# brain.net
KiCad netlist of a schematic drawn in EAGLE
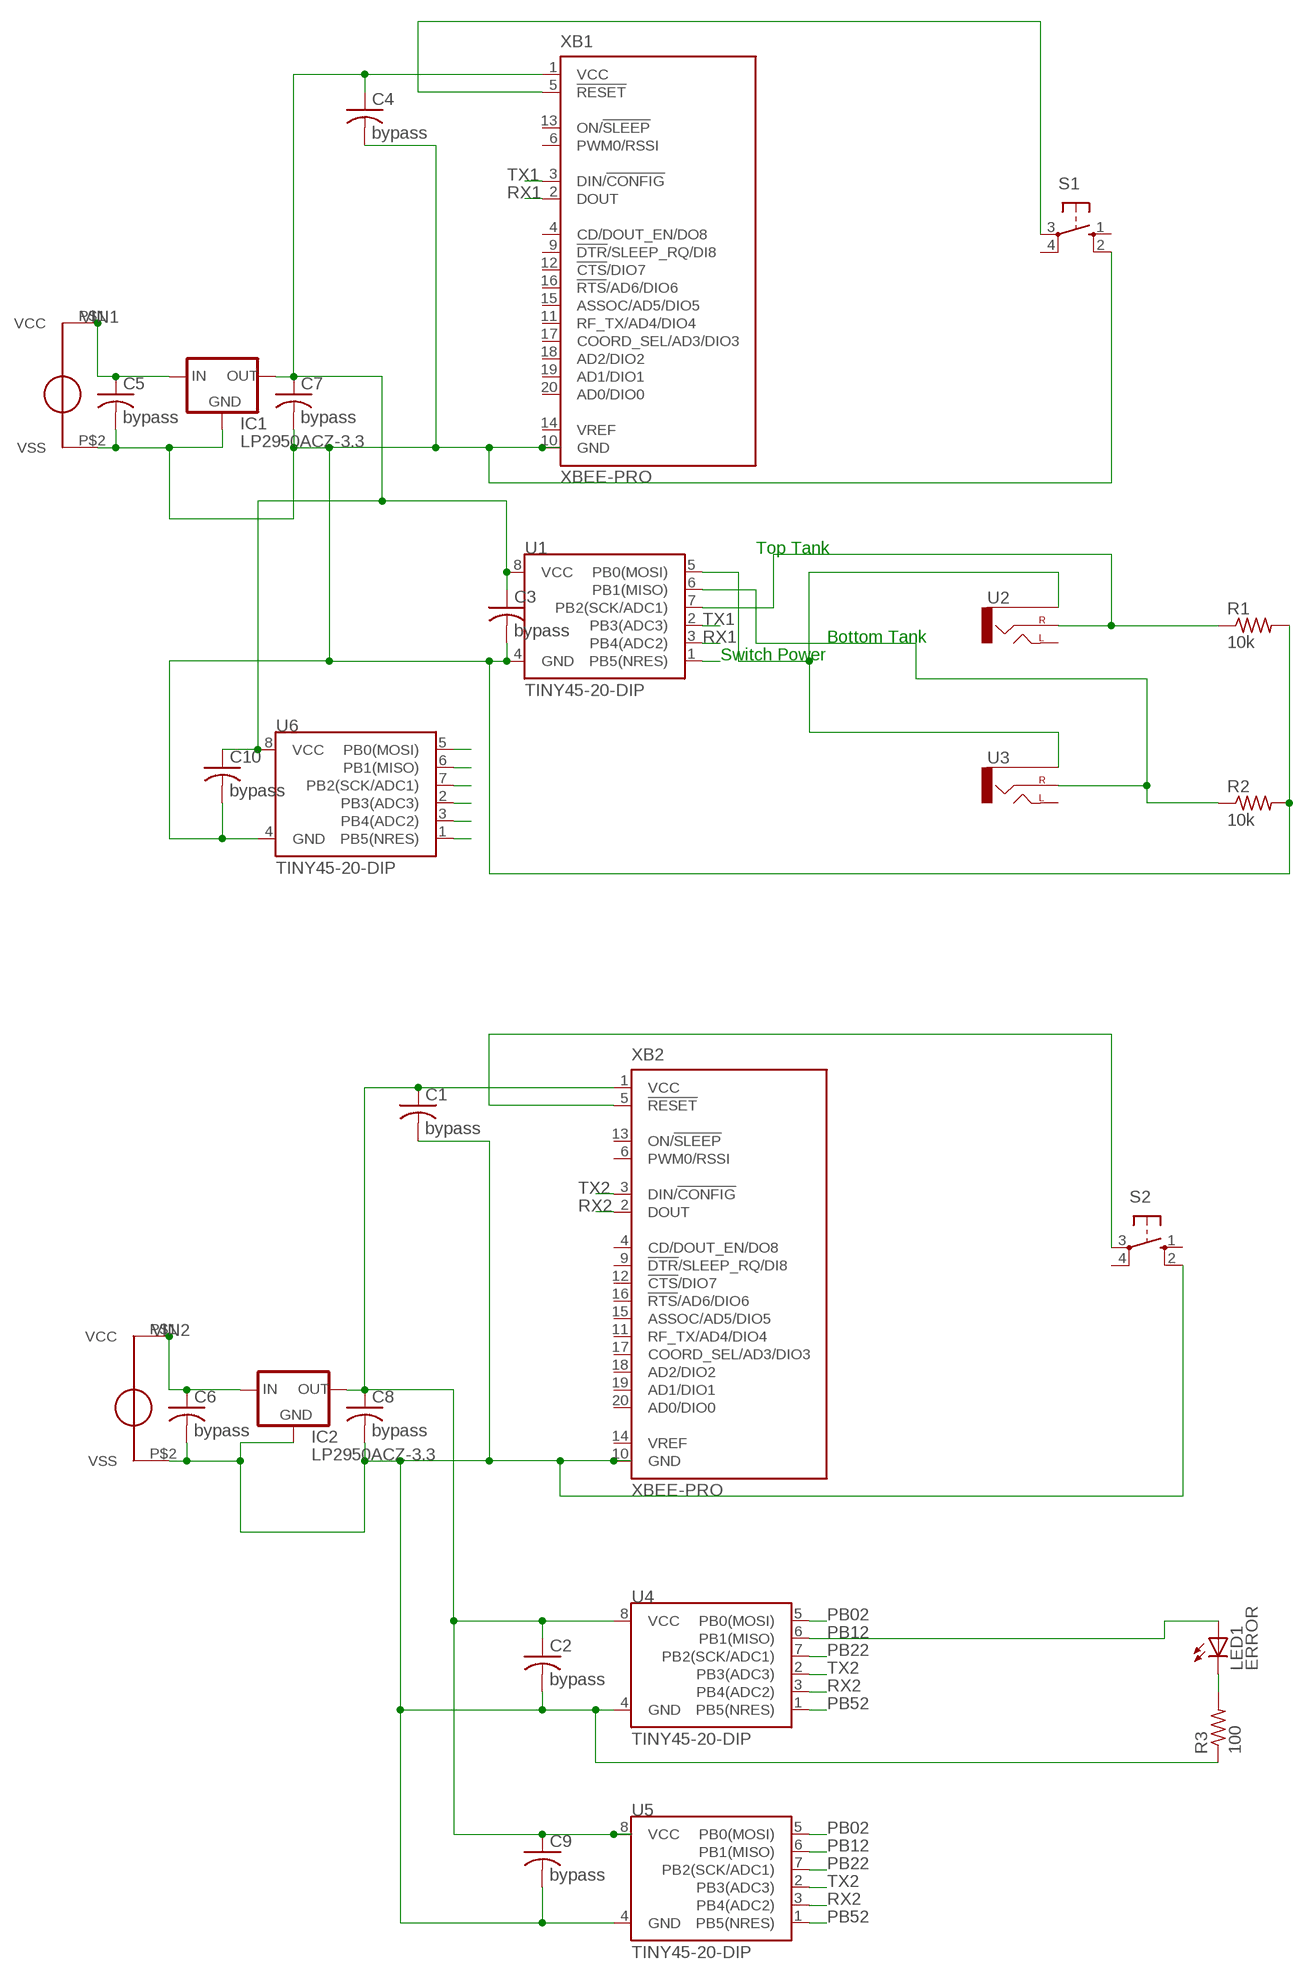
[diagram p0: schematic, sheet 1]

(export (version "E")
  (design (tool "Eeschema 10.0.6"))
  (components
    (comp (ref "C1")
      (value "bypass")
      (footprint "eagle-import:C050-025X075")
      (libsource (lib "eagle-import") (part "C-US050-025X075"))
    )
    (comp (ref "C2")
      (value "bypass")
      (footprint "eagle-import:C050-025X075")
      (libsource (lib "eagle-import") (part "C-US050-025X075"))
    )
    (comp (ref "C3")
      (value "bypass")
      (footprint "eagle-import:C050-025X075")
      (libsource (lib "eagle-import") (part "C-US050-025X075"))
    )
    (comp (ref "C4")
      (value "bypass")
      (footprint "eagle-import:C050-025X075")
      (libsource (lib "eagle-import") (part "C-US050-025X075"))
    )
    (comp (ref "C5")
      (value "bypass")
      (footprint "eagle-import:C050-025X075")
      (libsource (lib "eagle-import") (part "C-US050-025X075"))
    )
    (comp (ref "C6")
      (value "bypass")
      (footprint "eagle-import:C050-025X075")
      (libsource (lib "eagle-import") (part "C-US050-025X075"))
    )
    (comp (ref "C7")
      (value "bypass")
      (footprint "eagle-import:C050-025X075")
      (libsource (lib "eagle-import") (part "C-US050-025X075"))
    )
    (comp (ref "C8")
      (value "bypass")
      (footprint "eagle-import:C050-025X075")
      (libsource (lib "eagle-import") (part "C-US050-025X075"))
    )
    (comp (ref "C9")
      (value "bypass")
      (footprint "eagle-import:C050-025X075")
      (libsource (lib "eagle-import") (part "C-US050-025X075"))
    )
    (comp (ref "C10")
      (value "bypass")
      (footprint "eagle-import:C050-025X075")
      (libsource (lib "eagle-import") (part "C-US050-025X075"))
    )
    (comp (ref "IC1")
      (value "LP2950ACZ-3.3")
      (footprint "eagle-import:TO92")
      (libsource (lib "eagle-import") (part "LP2950?ACZ-3.3"))
    )
    (comp (ref "IC2")
      (value "LP2950ACZ-3.3")
      (footprint "eagle-import:TO92")
      (libsource (lib "eagle-import") (part "LP2950?ACZ-3.3"))
    )
    (comp (ref "LED1")
      (value "ERROR")
      (footprint "eagle-import:LED3MM")
      (libsource (lib "eagle-import") (part "LED3MM"))
    )
    (comp (ref "R1")
      (value "10k")
      (footprint "eagle-import:0207_10")
      (fields (field (name "MPN") "LT3652EMSE#PBF"))
      (libsource (lib "eagle-import") (part "R-US_0207/10"))
    )
    (comp (ref "R2")
      (value "10k")
      (footprint "eagle-import:0207_10")
      (fields (field (name "MPN") "LT3652EMSE#PBF"))
      (libsource (lib "eagle-import") (part "R-US_0207/10"))
    )
    (comp (ref "R3")
      (value "100")
      (footprint "eagle-import:0207_10")
      (fields (field (name "MPN") "LT3652EMSE#PBF"))
      (libsource (lib "eagle-import") (part "R-US_0207/10"))
    )
    (comp (ref "S1")
      (value "10-XX")
      (footprint "eagle-import:B3F-10XX")
      (fields (field (name "MPN") "B3F-1000"))
      (libsource (lib "eagle-import") (part "10-XX"))
    )
    (comp (ref "S2")
      (value "10-XX")
      (footprint "eagle-import:B3F-10XX")
      (fields (field (name "MPN") "B3F-1000"))
      (libsource (lib "eagle-import") (part "10-XX"))
    )
    (comp (ref "U$3")
      (value "SUNNYBUDDYMOUNT")
      (footprint "eagle-import:SUNNYBUDDYMOUNT")
      (libsource (lib "eagle-import") (part "SUNNYBUDDYMOUNT"))
    )
    (comp (ref "U$6")
      (value "SUNNYBUDDYMOUNT")
      (footprint "eagle-import:SUNNYBUDDYMOUNT")
      (libsource (lib "eagle-import") (part "SUNNYBUDDYMOUNT"))
    )
    (comp (ref "U1")
      (value "TINY45-20-DIP")
      (footprint "eagle-import:DIP08")
      (libsource (lib "eagle-import") (part "ATTINY45TINY45-20-DIP"))
    )
    (comp (ref "U2")
      (value "AUDIO-JACKPTH")
      (footprint "eagle-import:AUDIO-JACK")
      (libsource (lib "eagle-import") (part "AUDIO-JACKPTH"))
    )
    (comp (ref "U3")
      (value "AUDIO-JACKPTH")
      (footprint "eagle-import:AUDIO-JACK")
      (libsource (lib "eagle-import") (part "AUDIO-JACKPTH"))
    )
    (comp (ref "U4")
      (value "TINY45-20-DIP")
      (footprint "eagle-import:DIP08")
      (libsource (lib "eagle-import") (part "ATTINY45TINY45-20-DIP"))
    )
    (comp (ref "U5")
      (value "TINY45-20-DIP")
      (footprint "eagle-import:DIP08")
      (libsource (lib "eagle-import") (part "ATTINY45TINY45-20-DIP"))
    )
    (comp (ref "U6")
      (value "TINY45-20-DIP")
      (footprint "eagle-import:DIP08")
      (libsource (lib "eagle-import") (part "ATTINY45TINY45-20-DIP"))
    )
    (comp (ref "XB1")
      (value "XBEE-PRO")
      (footprint "eagle-import:XBEE-PRO")
      (fields (field (name "MPN") "XBP24-AWI-001") (field (name "OC_NEWARK") "unknown"))
      (libsource (lib "eagle-import") (part "XBEE-PRO"))
    )
    (comp (ref "XB2")
      (value "XBEE-PRO")
      (footprint "eagle-import:XBEE-PRO")
      (fields (field (name "MPN") "XBP24-AWI-001") (field (name "OC_NEWARK") "unknown"))
      (libsource (lib "eagle-import") (part "XBEE-PRO"))
    )
  )
  (nets
    (net (code "1") (name "/PB01") (class "Default")
      (node (ref "U1") (pin "5") (pinfunction "PB0(MOSI)_5") (pintype "bidirectional"))
      (node (ref "U2") (pin "SLEEVE") (pinfunction "SLEEVE_SLEEVE") (pintype "bidirectional"))
      (node (ref "U3") (pin "SLEEVE") (pinfunction "SLEEVE_SLEEVE") (pintype "bidirectional"))
      (node (ref "U6") (pin "5") (pinfunction "PB0(MOSI)_5") (pintype "bidirectional"))
    )
    (net (code "2") (name "/PB02") (class "Default")
      (node (ref "U4") (pin "5") (pinfunction "PB0(MOSI)_5") (pintype "bidirectional"))
      (node (ref "U5") (pin "5") (pinfunction "PB0(MOSI)_5") (pintype "bidirectional"))
    )
    (net (code "3") (name "/PB11") (class "Default")
      (node (ref "R2") (pin "1") (pinfunction "1_1") (pintype "passive"))
      (node (ref "U1") (pin "6") (pinfunction "PB1(MISO)_6") (pintype "bidirectional"))
      (node (ref "U3") (pin "RING") (pinfunction "RIGHT_RING") (pintype "bidirectional"))
      (node (ref "U6") (pin "6") (pinfunction "PB1(MISO)_6") (pintype "bidirectional"))
    )
    (net (code "4") (name "/PB12") (class "Default")
      (node (ref "LED1") (pin "A") (pinfunction "A_A") (pintype "passive"))
      (node (ref "U4") (pin "6") (pinfunction "PB1(MISO)_6") (pintype "bidirectional"))
      (node (ref "U5") (pin "6") (pinfunction "PB1(MISO)_6") (pintype "bidirectional"))
    )
    (net (code "5") (name "/PB21") (class "Default")
      (node (ref "R1") (pin "1") (pinfunction "1_1") (pintype "passive"))
      (node (ref "U1") (pin "7") (pinfunction "PB2(SCK/ADC1)_7") (pintype "bidirectional"))
      (node (ref "U2") (pin "RING") (pinfunction "RIGHT_RING") (pintype "bidirectional"))
      (node (ref "U6") (pin "7") (pinfunction "PB2(SCK/ADC1)_7") (pintype "bidirectional"))
    )
    (net (code "6") (name "/PB22") (class "Default")
      (node (ref "U4") (pin "7") (pinfunction "PB2(SCK/ADC1)_7") (pintype "bidirectional"))
      (node (ref "U5") (pin "7") (pinfunction "PB2(SCK/ADC1)_7") (pintype "bidirectional"))
    )
    (net (code "7") (name "/PB51") (class "Default")
      (node (ref "U1") (pin "1") (pinfunction "PB5(NRES)_1") (pintype "bidirectional"))
      (node (ref "U6") (pin "1") (pinfunction "PB5(NRES)_1") (pintype "bidirectional"))
    )
    (net (code "8") (name "/PB52") (class "Default")
      (node (ref "U4") (pin "1") (pinfunction "PB5(NRES)_1") (pintype "bidirectional"))
      (node (ref "U5") (pin "1") (pinfunction "PB5(NRES)_1") (pintype "bidirectional"))
    )
    (net (code "9") (name "/RX1") (class "Default")
      (node (ref "U1") (pin "3") (pinfunction "PB4(ADC2)_3") (pintype "bidirectional"))
      (node (ref "U6") (pin "3") (pinfunction "PB4(ADC2)_3") (pintype "bidirectional"))
      (node (ref "XB1") (pin "2") (pinfunction "DOUT_2") (pintype "output"))
    )
    (net (code "10") (name "/RX2") (class "Default")
      (node (ref "U4") (pin "3") (pinfunction "PB4(ADC2)_3") (pintype "bidirectional"))
      (node (ref "U5") (pin "3") (pinfunction "PB4(ADC2)_3") (pintype "bidirectional"))
      (node (ref "XB2") (pin "2") (pinfunction "DOUT_2") (pintype "output"))
    )
    (net (code "11") (name "/TX1") (class "Default")
      (node (ref "U1") (pin "2") (pinfunction "PB3(ADC3)_2") (pintype "bidirectional"))
      (node (ref "U6") (pin "2") (pinfunction "PB3(ADC3)_2") (pintype "bidirectional"))
      (node (ref "XB1") (pin "3") (pinfunction "DIN/~{CONFIG}_3") (pintype "input"))
    )
    (net (code "12") (name "/TX2") (class "Default")
      (node (ref "U4") (pin "2") (pinfunction "PB3(ADC3)_2") (pintype "bidirectional"))
      (node (ref "U5") (pin "2") (pinfunction "PB3(ADC3)_2") (pintype "bidirectional"))
      (node (ref "XB2") (pin "3") (pinfunction "DIN/~{CONFIG}_3") (pintype "input"))
    )
    (net (code "13") (name "/VIN1") (class "Default")
      (node (ref "C5") (pin "1") (pinfunction "1_1") (pintype "passive"))
      (node (ref "IC1") (pin "3") (pinfunction "IN_3") (pintype "input"))
      (node (ref "U$3") (pin "P$1") (pinfunction "VCC_P$1") (pintype "bidirectional"))
    )
    (net (code "14") (name "/VIN2") (class "Default")
      (node (ref "C6") (pin "1") (pinfunction "1_1") (pintype "passive"))
      (node (ref "IC2") (pin "3") (pinfunction "IN_3") (pintype "input"))
      (node (ref "U$6") (pin "P$1") (pinfunction "VCC_P$1") (pintype "bidirectional"))
    )
    (net (code "15") (name "Net-(IC1-GND)") (class "Default")
      (node (ref "C10") (pin "2") (pinfunction "2_2") (pintype "passive"))
      (node (ref "C3") (pin "2") (pinfunction "2_2") (pintype "passive"))
      (node (ref "C4") (pin "2") (pinfunction "2_2") (pintype "passive"))
      (node (ref "C5") (pin "2") (pinfunction "2_2") (pintype "passive"))
      (node (ref "C7") (pin "2") (pinfunction "2_2") (pintype "passive"))
      (node (ref "IC1") (pin "2") (pinfunction "GND_2") (pintype "input"))
      (node (ref "R1") (pin "2") (pinfunction "2_2") (pintype "passive"))
      (node (ref "R2") (pin "2") (pinfunction "2_2") (pintype "passive"))
      (node (ref "S1") (pin "2") (pinfunction "S1_2") (pintype "passive"))
      (node (ref "U$3") (pin "P$2") (pinfunction "VSS_P$2") (pintype "bidirectional"))
      (node (ref "U1") (pin "4") (pinfunction "GND_4") (pintype "bidirectional"))
      (node (ref "U6") (pin "4") (pinfunction "GND_4") (pintype "bidirectional"))
      (node (ref "XB1") (pin "10") (pinfunction "GND_10") (pintype "power_in"))
    )
    (net (code "16") (name "Net-(IC1-OUT)") (class "Default")
      (node (ref "C10") (pin "1") (pinfunction "1_1") (pintype "passive"))
      (node (ref "C3") (pin "1") (pinfunction "1_1") (pintype "passive"))
      (node (ref "C4") (pin "1") (pinfunction "1_1") (pintype "passive"))
      (node (ref "C7") (pin "1") (pinfunction "1_1") (pintype "passive"))
      (node (ref "IC1") (pin "1") (pinfunction "OUT_1") (pintype "passive"))
      (node (ref "U1") (pin "8") (pinfunction "VCC_8") (pintype "bidirectional"))
      (node (ref "U6") (pin "8") (pinfunction "VCC_8") (pintype "bidirectional"))
      (node (ref "XB1") (pin "1") (pinfunction "VCC_1") (pintype "power_in"))
    )
    (net (code "17") (name "Net-(IC2-GND)") (class "Default")
      (node (ref "C1") (pin "2") (pinfunction "2_2") (pintype "passive"))
      (node (ref "C2") (pin "2") (pinfunction "2_2") (pintype "passive"))
      (node (ref "C6") (pin "2") (pinfunction "2_2") (pintype "passive"))
      (node (ref "C8") (pin "2") (pinfunction "2_2") (pintype "passive"))
      (node (ref "C9") (pin "2") (pinfunction "2_2") (pintype "passive"))
      (node (ref "IC2") (pin "2") (pinfunction "GND_2") (pintype "input"))
      (node (ref "R3") (pin "1") (pinfunction "1_1") (pintype "passive"))
      (node (ref "S2") (pin "2") (pinfunction "S1_2") (pintype "passive"))
      (node (ref "U$6") (pin "P$2") (pinfunction "VSS_P$2") (pintype "bidirectional"))
      (node (ref "U4") (pin "4") (pinfunction "GND_4") (pintype "bidirectional"))
      (node (ref "U5") (pin "4") (pinfunction "GND_4") (pintype "bidirectional"))
      (node (ref "XB2") (pin "10") (pinfunction "GND_10") (pintype "power_in"))
    )
    (net (code "18") (name "Net-(IC2-OUT)") (class "Default")
      (node (ref "C1") (pin "1") (pinfunction "1_1") (pintype "passive"))
      (node (ref "C2") (pin "1") (pinfunction "1_1") (pintype "passive"))
      (node (ref "C8") (pin "1") (pinfunction "1_1") (pintype "passive"))
      (node (ref "C9") (pin "1") (pinfunction "1_1") (pintype "passive"))
      (node (ref "IC2") (pin "1") (pinfunction "OUT_1") (pintype "passive"))
      (node (ref "U4") (pin "8") (pinfunction "VCC_8") (pintype "bidirectional"))
      (node (ref "U5") (pin "8") (pinfunction "VCC_8") (pintype "bidirectional"))
      (node (ref "XB2") (pin "1") (pinfunction "VCC_1") (pintype "power_in"))
    )
    (net (code "19") (name "Net-(LED1-C)") (class "Default")
      (node (ref "LED1") (pin "K") (pinfunction "C_K") (pintype "passive"))
      (node (ref "R3") (pin "2") (pinfunction "2_2") (pintype "passive"))
    )
    (net (code "20") (name "Net-(S1-P)") (class "Default")
      (node (ref "S1") (pin "3") (pinfunction "P_3") (pintype "passive"))
      (node (ref "XB1") (pin "5") (pinfunction "~{RESET}_5") (pintype "input"))
    )
    (net (code "21") (name "Net-(S2-P)") (class "Default")
      (node (ref "S2") (pin "3") (pinfunction "P_3") (pintype "passive"))
      (node (ref "XB2") (pin "5") (pinfunction "~{RESET}_5") (pintype "input"))
    )
    (net (code "22") (name "unconnected-(S1-P1-Pad4)") (class "Default")
      (node (ref "S1") (pin "4") (pinfunction "P1_4") (pintype "passive"))
    )
    (net (code "23") (name "unconnected-(S1-S-Pad1)") (class "Default")
      (node (ref "S1") (pin "1") (pinfunction "S_1") (pintype "passive"))
    )
    (net (code "24") (name "unconnected-(S2-P1-Pad4)") (class "Default")
      (node (ref "S2") (pin "4") (pinfunction "P1_4") (pintype "passive"))
    )
    (net (code "25") (name "unconnected-(S2-S-Pad1)") (class "Default")
      (node (ref "S2") (pin "1") (pinfunction "S_1") (pintype "passive"))
    )
    (net (code "26") (name "unconnected-(U2-LEFT-PadTIP)") (class "Default")
      (node (ref "U2") (pin "TIP") (pinfunction "LEFT_TIP") (pintype "bidirectional"))
    )
    (net (code "27") (name "unconnected-(U3-LEFT-PadTIP)") (class "Default")
      (node (ref "U3") (pin "TIP") (pinfunction "LEFT_TIP") (pintype "bidirectional"))
    )
    (net (code "28") (name "unconnected-(XB1-AD0{slash}DIO0-Pad20)") (class "Default")
      (node (ref "XB1") (pin "20") (pinfunction "AD0/DIO0_20") (pintype "bidirectional"))
    )
    (net (code "29") (name "unconnected-(XB1-AD1{slash}DIO1-Pad19)") (class "Default")
      (node (ref "XB1") (pin "19") (pinfunction "AD1/DIO1_19") (pintype "bidirectional"))
    )
    (net (code "30") (name "unconnected-(XB1-AD2{slash}DIO2-Pad18)") (class "Default")
      (node (ref "XB1") (pin "18") (pinfunction "AD2/DIO2_18") (pintype "bidirectional"))
    )
    (net (code "31") (name "unconnected-(XB1-ASSOC{slash}AD5{slash}DIO5-Pad15)") (class "Default")
      (node (ref "XB1") (pin "15") (pinfunction "ASSOC/AD5/DIO5_15") (pintype "bidirectional"))
    )
    (net (code "32") (name "unconnected-(XB1-CD{slash}DOUT_EN{slash}DO8-Pad4)") (class "Default")
      (node (ref "XB1") (pin "4") (pinfunction "CD/DOUT_EN/DO8_4") (pintype "output"))
    )
    (net (code "33") (name "unconnected-(XB1-COORD_SEL{slash}AD3{slash}DIO3-Pad17)") (class "Default")
      (node (ref "XB1") (pin "17") (pinfunction "COORD_SEL/AD3/DIO3_17") (pintype "bidirectional"))
    )
    (net (code "34") (name "unconnected-(XB1-ON{slash}~{SLEEP}-Pad13)") (class "Default")
      (node (ref "XB1") (pin "13") (pinfunction "ON/~{SLEEP}_13") (pintype "output"))
    )
    (net (code "35") (name "unconnected-(XB1-PWM0{slash}RSSI-Pad6)") (class "Default")
      (node (ref "XB1") (pin "6") (pinfunction "PWM0/RSSI_6") (pintype "output"))
    )
    (net (code "36") (name "unconnected-(XB1-RF_TX{slash}AD4{slash}DIO4-Pad11)") (class "Default")
      (node (ref "XB1") (pin "11") (pinfunction "RF_TX/AD4/DIO4_11") (pintype "bidirectional"))
    )
    (net (code "37") (name "unconnected-(XB1-VREF-Pad14)") (class "Default")
      (node (ref "XB1") (pin "14") (pinfunction "VREF_14") (pintype "input"))
    )
    (net (code "38") (name "unconnected-(XB1-~{CTS}{slash}DIO7-Pad12)") (class "Default")
      (node (ref "XB1") (pin "12") (pinfunction "~{CTS}/DIO7_12") (pintype "bidirectional"))
    )
    (net (code "39") (name "unconnected-(XB1-~{DTR}{slash}SLEEP_RQ{slash}DI8-Pad9)") (class "Default")
      (node (ref "XB1") (pin "9") (pinfunction "~{DTR}/SLEEP_RQ/DI8_9") (pintype "bidirectional"))
    )
    (net (code "40") (name "unconnected-(XB1-~{RTS}{slash}AD6{slash}DIO6-Pad16)") (class "Default")
      (node (ref "XB1") (pin "16") (pinfunction "~{RTS}/AD6/DIO6_16") (pintype "bidirectional"))
    )
    (net (code "41") (name "unconnected-(XB2-AD0{slash}DIO0-Pad20)") (class "Default")
      (node (ref "XB2") (pin "20") (pinfunction "AD0/DIO0_20") (pintype "bidirectional"))
    )
    (net (code "42") (name "unconnected-(XB2-AD1{slash}DIO1-Pad19)") (class "Default")
      (node (ref "XB2") (pin "19") (pinfunction "AD1/DIO1_19") (pintype "bidirectional"))
    )
    (net (code "43") (name "unconnected-(XB2-AD2{slash}DIO2-Pad18)") (class "Default")
      (node (ref "XB2") (pin "18") (pinfunction "AD2/DIO2_18") (pintype "bidirectional"))
    )
    (net (code "44") (name "unconnected-(XB2-ASSOC{slash}AD5{slash}DIO5-Pad15)") (class "Default")
      (node (ref "XB2") (pin "15") (pinfunction "ASSOC/AD5/DIO5_15") (pintype "bidirectional"))
    )
    (net (code "45") (name "unconnected-(XB2-CD{slash}DOUT_EN{slash}DO8-Pad4)") (class "Default")
      (node (ref "XB2") (pin "4") (pinfunction "CD/DOUT_EN/DO8_4") (pintype "output"))
    )
    (net (code "46") (name "unconnected-(XB2-COORD_SEL{slash}AD3{slash}DIO3-Pad17)") (class "Default")
      (node (ref "XB2") (pin "17") (pinfunction "COORD_SEL/AD3/DIO3_17") (pintype "bidirectional"))
    )
    (net (code "47") (name "unconnected-(XB2-ON{slash}~{SLEEP}-Pad13)") (class "Default")
      (node (ref "XB2") (pin "13") (pinfunction "ON/~{SLEEP}_13") (pintype "output"))
    )
    (net (code "48") (name "unconnected-(XB2-PWM0{slash}RSSI-Pad6)") (class "Default")
      (node (ref "XB2") (pin "6") (pinfunction "PWM0/RSSI_6") (pintype "output"))
    )
    (net (code "49") (name "unconnected-(XB2-RF_TX{slash}AD4{slash}DIO4-Pad11)") (class "Default")
      (node (ref "XB2") (pin "11") (pinfunction "RF_TX/AD4/DIO4_11") (pintype "bidirectional"))
    )
    (net (code "50") (name "unconnected-(XB2-VREF-Pad14)") (class "Default")
      (node (ref "XB2") (pin "14") (pinfunction "VREF_14") (pintype "input"))
    )
    (net (code "51") (name "unconnected-(XB2-~{CTS}{slash}DIO7-Pad12)") (class "Default")
      (node (ref "XB2") (pin "12") (pinfunction "~{CTS}/DIO7_12") (pintype "bidirectional"))
    )
    (net (code "52") (name "unconnected-(XB2-~{DTR}{slash}SLEEP_RQ{slash}DI8-Pad9)") (class "Default")
      (node (ref "XB2") (pin "9") (pinfunction "~{DTR}/SLEEP_RQ/DI8_9") (pintype "bidirectional"))
    )
    (net (code "53") (name "unconnected-(XB2-~{RTS}{slash}AD6{slash}DIO6-Pad16)") (class "Default")
      (node (ref "XB2") (pin "16") (pinfunction "~{RTS}/AD6/DIO6_16") (pintype "bidirectional"))
    )
  )
)
